# CarBee_v1_1.net
KiCad netlist of a schematic drawn in EAGLE
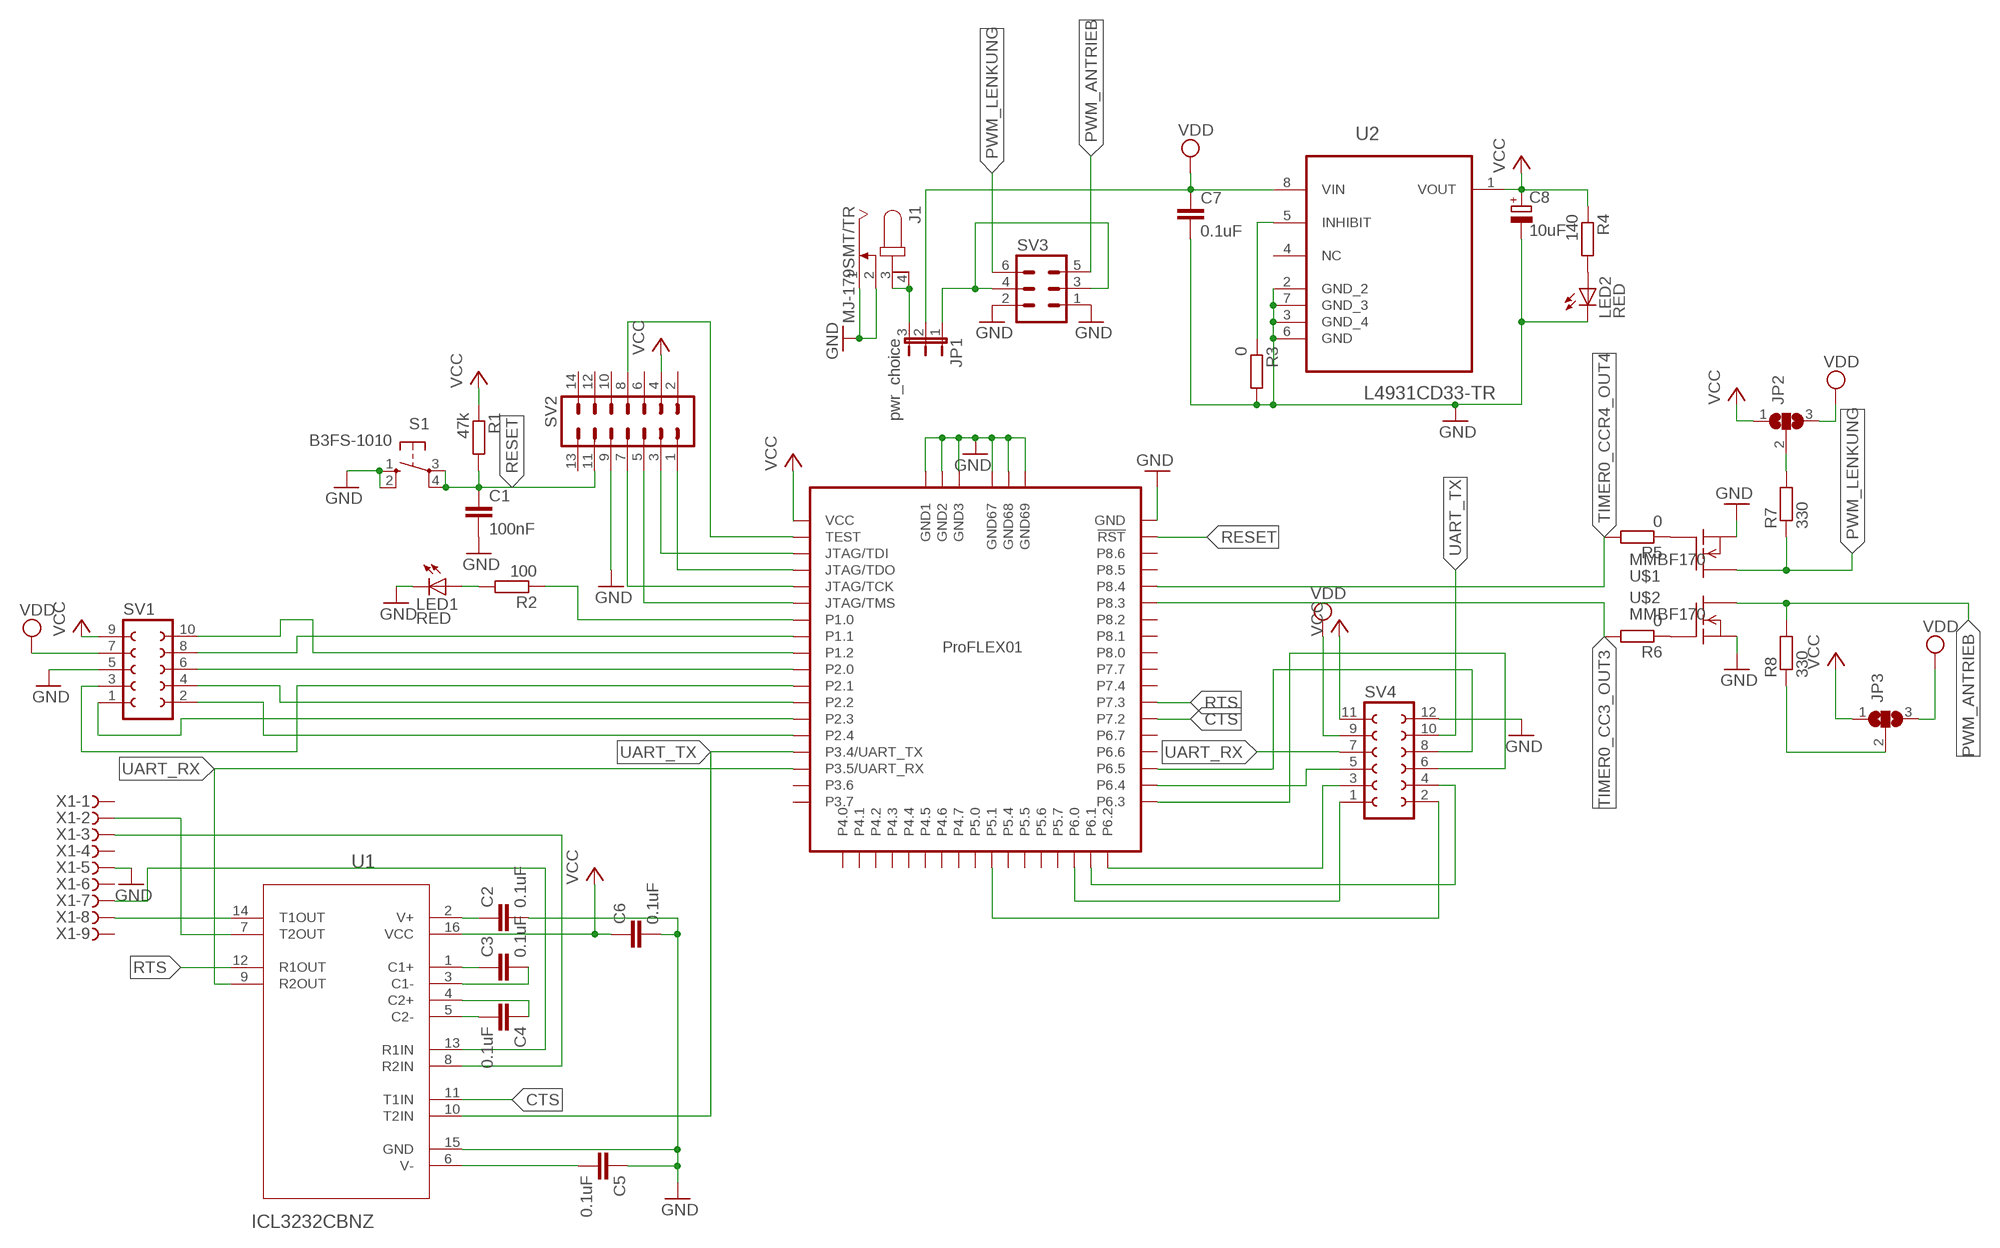
[diagram p0: schematic, sheet 1]

(export (version "E")
  (design (tool "Eeschema 10.0.6"))
  (components
    (comp (ref "C1")
      (value "100nF")
      (footprint "eagle-import:C0603")
      (fields (field (name "MPN") "0306ZC104KAT2A"))
      (libsource (lib "eagle-import") (part "C-EUC0603"))
    )
    (comp (ref "C2")
      (value "0.1uF")
      (footprint "eagle-import:C0603")
      (libsource (lib "eagle-import") (part "C-EUC0603"))
    )
    (comp (ref "C3")
      (value "0.1uF")
      (footprint "eagle-import:C0603")
      (fields (field (name "MPN") "0306ZC104KAT2A"))
      (libsource (lib "eagle-import") (part "C-EUC0603"))
    )
    (comp (ref "C4")
      (value "0.1uF")
      (footprint "eagle-import:C0603")
      (libsource (lib "eagle-import") (part "C-EUC0603"))
    )
    (comp (ref "C5")
      (value "0.1uF")
      (footprint "eagle-import:C0603")
      (libsource (lib "eagle-import") (part "C-EUC0603"))
    )
    (comp (ref "C6")
      (value "0.1uF")
      (footprint "eagle-import:C0603")
      (fields (field (name "MPN") "0306ZC104KAT2A"))
      (libsource (lib "eagle-import") (part "C-EUC0603"))
    )
    (comp (ref "C7")
      (value "0.1uF")
      (footprint "eagle-import:C0603")
      (libsource (lib "eagle-import") (part "C-EUC0603"))
    )
    (comp (ref "C8")
      (value "10uF")
      (footprint "eagle-import:PANASONIC_B")
      (libsource (lib "eagle-import") (part "CPOL-EU"))
    )
    (comp (ref "J1")
      (value "MJ-179SMT/TR")
      (footprint "eagle-import:MJ-179SMT")
      (libsource (lib "eagle-import") (part "MJ-179SMT/TR"))
    )
    (comp (ref "JP1")
      (value "pwr_choice")
      (footprint "eagle-import:JP2")
      (libsource (lib "eagle-import") (part "JP2E"))
    )
    (comp (ref "JP2")
      (value "SJ2W")
      (footprint "eagle-import:SJ_2")
      (libsource (lib "eagle-import") (part "SJ2W"))
    )
    (comp (ref "JP3")
      (value "SJ2W")
      (footprint "eagle-import:SJ_2")
      (libsource (lib "eagle-import") (part "SJ2W"))
    )
    (comp (ref "LED1")
      (value "RED")
      (footprint "eagle-import:CHIP-LED0603")
      (libsource (lib "eagle-import") (part "LEDCHIP-LED0603"))
    )
    (comp (ref "LED2")
      (value "RED")
      (footprint "eagle-import:CHIP-LED0603")
      (libsource (lib "eagle-import") (part "LEDCHIP-LED0603"))
    )
    (comp (ref "MOD1")
      (value "PROFLEX01")
      (footprint "eagle-import:MODFLEX01")
      (libsource (lib "eagle-import") (part "PROFLEX01"))
    )
    (comp (ref "R1")
      (value "47k")
      (footprint "eagle-import:R0603")
      (libsource (lib "eagle-import") (part "R-EU_R0603"))
    )
    (comp (ref "R2")
      (value "100")
      (footprint "eagle-import:R0603")
      (libsource (lib "eagle-import") (part "R-EU_R0603"))
    )
    (comp (ref "R3")
      (value "0")
      (footprint "eagle-import:R0603")
      (libsource (lib "eagle-import") (part "R-EU_R0603"))
    )
    (comp (ref "R4")
      (value "140")
      (footprint "eagle-import:R0603")
      (libsource (lib "eagle-import") (part "R-EU_R0603"))
    )
    (comp (ref "R5")
      (value "0")
      (footprint "eagle-import:R0603")
      (libsource (lib "eagle-import") (part "R-EU_R0603"))
    )
    (comp (ref "R6")
      (value "0")
      (footprint "eagle-import:R0603")
      (libsource (lib "eagle-import") (part "R-EU_R0603"))
    )
    (comp (ref "R7")
      (value "330")
      (footprint "eagle-import:R0603")
      (libsource (lib "eagle-import") (part "R-EU_R0603"))
    )
    (comp (ref "R8")
      (value "330")
      (footprint "eagle-import:R0603")
      (libsource (lib "eagle-import") (part "R-EU_R0603"))
    )
    (comp (ref "S1")
      (value "B3FS-1010")
      (footprint "eagle-import:B3FS-1010")
      (libsource (lib "eagle-import") (part "B3FS-1010"))
    )
    (comp (ref "SV1")
      (value "FE05-2")
      (footprint "eagle-import:FE05-2")
      (libsource (lib "eagle-import") (part "FE05-2"))
    )
    (comp (ref "SV2")
      (value "ML14")
      (footprint "eagle-import:ML14")
      (libsource (lib "eagle-import") (part "ML14"))
    )
    (comp (ref "SV3")
      (value "MA03-2")
      (footprint "eagle-import:MA03-2")
      (libsource (lib "eagle-import") (part "MA03-2"))
    )
    (comp (ref "SV4")
      (value "FE06-2")
      (footprint "eagle-import:FE06-2")
      (libsource (lib "eagle-import") (part "FE06-2"))
    )
    (comp (ref "U$1")
      (value "MMBF170")
      (footprint "eagle-import:SOT23")
      (libsource (lib "eagle-import") (part "MMBF170"))
    )
    (comp (ref "U$2")
      (value "MMBF170")
      (footprint "eagle-import:SOT23")
      (libsource (lib "eagle-import") (part "MMBF170"))
    )
    (comp (ref "U1")
      (value "ICL3232CBNZ")
      (footprint "eagle-import:SOIC127P600X175-16N")
      (libsource (lib "eagle-import") (part "ICL3232CBNZ"))
    )
    (comp (ref "U2")
      (value "L4931CD33-TR")
      (footprint "eagle-import:SOIC127P600X175-8N")
      (libsource (lib "eagle-import") (part "L4931CD33-TR"))
    )
    (comp (ref "X1")
      (value "F09HPS")
      (footprint "eagle-import:F09HP")
      (libsource (lib "eagle-import") (part "F09?SHP"))
    )
  )
  (nets
    (net (code "1") (name "CTS") (class "Default")
      (node (ref "MOD1") (pin "P$37") (pinfunction "P7.2_P$37") (pintype "bidirectional"))
      (node (ref "U1") (pin "11") (pinfunction "T1IN_11") (pintype "input"))
    )
    (net (code "2") (name "GND") (class "Default")
      (node (ref "C1") (pin "2") (pinfunction "2_2") (pintype "passive"))
      (node (ref "C2") (pin "2") (pinfunction "2_2") (pintype "passive"))
      (node (ref "C5") (pin "1") (pinfunction "1_1") (pintype "passive"))
      (node (ref "C6") (pin "2") (pinfunction "2_2") (pintype "passive"))
      (node (ref "C7") (pin "2") (pinfunction "2_2") (pintype "passive"))
      (node (ref "C8") (pin "-") (pinfunction "-_-") (pintype "passive"))
      (node (ref "J1") (pin "1") (pinfunction "1_1") (pintype "passive"))
      (node (ref "J1") (pin "2") (pinfunction "2_2") (pintype "passive"))
      (node (ref "LED1") (pin "C") (pinfunction "C_C") (pintype "passive"))
      (node (ref "LED2") (pin "C") (pinfunction "C_C") (pintype "passive"))
      (node (ref "MOD1") (pin "P$1") (pinfunction "GND1_P$1") (pintype "bidirectional"))
      (node (ref "MOD1") (pin "P$2") (pinfunction "GND2_P$2") (pintype "bidirectional"))
      (node (ref "MOD1") (pin "P$3") (pinfunction "GND3_P$3") (pintype "bidirectional"))
      (node (ref "MOD1") (pin "P$44") (pinfunction "GND_P$44") (pintype "bidirectional"))
      (node (ref "MOD1") (pin "P$67") (pinfunction "GND67_P$67") (pintype "bidirectional"))
      (node (ref "MOD1") (pin "P$68") (pinfunction "GND68_P$68") (pintype "bidirectional"))
      (node (ref "MOD1") (pin "P$69") (pinfunction "GND69_P$69") (pintype "bidirectional"))
      (node (ref "R3") (pin "2") (pinfunction "2_2") (pintype "passive"))
      (node (ref "S1") (pin "1") (pinfunction "S_1") (pintype "passive"))
      (node (ref "S1") (pin "2") (pinfunction "S1_2") (pintype "passive"))
      (node (ref "SV1") (pin "5") (pinfunction "5_5") (pintype "passive"))
      (node (ref "SV2") (pin "9") (pinfunction "9_9") (pintype "passive"))
      (node (ref "SV3") (pin "1") (pinfunction "1_1") (pintype "passive"))
      (node (ref "SV3") (pin "2") (pinfunction "2_2") (pintype "passive"))
      (node (ref "SV4") (pin "12") (pinfunction "12_12") (pintype "passive"))
      (node (ref "U$1") (pin "2") (pinfunction "S_2") (pintype "passive"))
      (node (ref "U$2") (pin "2") (pinfunction "S_2") (pintype "passive"))
      (node (ref "U1") (pin "15") (pinfunction "GND_15") (pintype "passive"))
      (node (ref "U2") (pin "2") (pinfunction "GND_2_2") (pintype "passive"))
      (node (ref "U2") (pin "3") (pinfunction "GND_4_3") (pintype "passive"))
      (node (ref "U2") (pin "6") (pinfunction "GND_6") (pintype "passive"))
      (node (ref "U2") (pin "7") (pinfunction "GND_3_7") (pintype "passive"))
      (node (ref "X1") (pin "5") (pinfunction "F_5") (pintype "passive"))
    )
    (net (code "3") (name "Net-(J1-Pad3)") (class "Default")
      (node (ref "J1") (pin "3") (pinfunction "3_3") (pintype "passive"))
      (node (ref "J1") (pin "4") (pinfunction "4_4") (pintype "passive"))
      (node (ref "JP1") (pin "3") (pinfunction "3_3") (pintype "passive"))
    )
    (net (code "4") (name "Net-(JP1-Pad1)") (class "Default")
      (node (ref "JP1") (pin "1") (pinfunction "1_1") (pintype "passive"))
      (node (ref "SV3") (pin "3") (pinfunction "3_3") (pintype "passive"))
      (node (ref "SV3") (pin "4") (pinfunction "4_4") (pintype "passive"))
    )
    (net (code "5") (name "Net-(JP2-Pad2)") (class "Default")
      (node (ref "JP2") (pin "2") (pinfunction "2_2") (pintype "passive"))
      (node (ref "R7") (pin "2") (pinfunction "2_2") (pintype "passive"))
    )
    (net (code "6") (name "Net-(JP3-Pad2)") (class "Default")
      (node (ref "JP3") (pin "2") (pinfunction "2_2") (pintype "passive"))
      (node (ref "R8") (pin "1") (pinfunction "1_1") (pintype "passive"))
    )
    (net (code "7") (name "Net-(LED1-PadA)") (class "Default")
      (node (ref "LED1") (pin "A") (pinfunction "A_A") (pintype "passive"))
      (node (ref "R2") (pin "2") (pinfunction "2_2") (pintype "passive"))
    )
    (net (code "8") (name "Net-(LED2-PadA)") (class "Default")
      (node (ref "LED2") (pin "A") (pinfunction "A_A") (pintype "passive"))
      (node (ref "R4") (pin "2") (pinfunction "2_2") (pintype "passive"))
    )
    (net (code "9") (name "Net-(MOD1-JTAG{slash}TCK)") (class "Default")
      (node (ref "MOD1") (pin "P$11") (pinfunction "JTAG/TCK_P$11") (pintype "bidirectional"))
      (node (ref "SV2") (pin "7") (pinfunction "7_7") (pintype "passive"))
    )
    (net (code "10") (name "Net-(MOD1-JTAG{slash}TDI)") (class "Default")
      (node (ref "MOD1") (pin "P$10") (pinfunction "JTAG/TDI_P$10") (pintype "bidirectional"))
      (node (ref "SV2") (pin "3") (pinfunction "3_3") (pintype "passive"))
    )
    (net (code "11") (name "Net-(MOD1-JTAG{slash}TDO)") (class "Default")
      (node (ref "MOD1") (pin "P$12") (pinfunction "JTAG/TDO_P$12") (pintype "bidirectional"))
      (node (ref "SV2") (pin "1") (pinfunction "1_1") (pintype "passive"))
    )
    (net (code "12") (name "Net-(MOD1-JTAG{slash}TMS)") (class "Default")
      (node (ref "MOD1") (pin "P$9") (pinfunction "JTAG/TMS_P$9") (pintype "bidirectional"))
      (node (ref "SV2") (pin "5") (pinfunction "5_5") (pintype "passive"))
    )
    (net (code "13") (name "Net-(MOD1-P1.0)") (class "Default")
      (node (ref "MOD1") (pin "P$49") (pinfunction "P1.0_P$49") (pintype "bidirectional"))
      (node (ref "R2") (pin "1") (pinfunction "1_1") (pintype "passive"))
    )
    (net (code "14") (name "Net-(MOD1-P1.1)") (class "Default")
      (node (ref "MOD1") (pin "P$50") (pinfunction "P1.1_P$50") (pintype "bidirectional"))
      (node (ref "SV1") (pin "8") (pinfunction "8_8") (pintype "passive"))
    )
    (net (code "15") (name "Net-(MOD1-P1.2)") (class "Default")
      (node (ref "MOD1") (pin "P$47") (pinfunction "P1.2_P$47") (pintype "bidirectional"))
      (node (ref "SV1") (pin "10") (pinfunction "10_10") (pintype "passive"))
    )
    (net (code "16") (name "Net-(MOD1-P2.0)") (class "Default")
      (node (ref "MOD1") (pin "P$51") (pinfunction "P2.0_P$51") (pintype "bidirectional"))
      (node (ref "SV1") (pin "6") (pinfunction "6_6") (pintype "passive"))
    )
    (net (code "17") (name "Net-(MOD1-P2.1)") (class "Default")
      (node (ref "MOD1") (pin "P$52") (pinfunction "P2.1_P$52") (pintype "bidirectional"))
      (node (ref "SV1") (pin "3") (pinfunction "3_3") (pintype "passive"))
    )
    (net (code "18") (name "Net-(MOD1-P2.2)") (class "Default")
      (node (ref "MOD1") (pin "P$53") (pinfunction "P2.2_P$53") (pintype "bidirectional"))
      (node (ref "SV1") (pin "4") (pinfunction "4_4") (pintype "passive"))
    )
    (net (code "19") (name "Net-(MOD1-P2.3)") (class "Default")
      (node (ref "MOD1") (pin "P$54") (pinfunction "P2.3_P$54") (pintype "bidirectional"))
      (node (ref "SV1") (pin "1") (pinfunction "1_1") (pintype "passive"))
    )
    (net (code "20") (name "Net-(MOD1-P2.4)") (class "Default")
      (node (ref "MOD1") (pin "P$55") (pinfunction "P2.4_P$55") (pintype "bidirectional"))
      (node (ref "SV1") (pin "2") (pinfunction "2_2") (pintype "passive"))
    )
    (net (code "21") (name "Net-(MOD1-P5.1)") (class "Default")
      (node (ref "MOD1") (pin "P$16") (pinfunction "P5.1_P$16") (pintype "bidirectional"))
      (node (ref "SV4") (pin "2") (pinfunction "2_2") (pintype "passive"))
    )
    (net (code "22") (name "Net-(MOD1-P6.0)") (class "Default")
      (node (ref "MOD1") (pin "P$17") (pinfunction "P6.0_P$17") (pintype "bidirectional"))
      (node (ref "SV4") (pin "1") (pinfunction "1_1") (pintype "passive"))
    )
    (net (code "23") (name "Net-(MOD1-P6.1)") (class "Default")
      (node (ref "MOD1") (pin "P$18") (pinfunction "P6.1_P$18") (pintype "bidirectional"))
      (node (ref "SV4") (pin "4") (pinfunction "4_4") (pintype "passive"))
    )
    (net (code "24") (name "Net-(MOD1-P6.2)") (class "Default")
      (node (ref "MOD1") (pin "P$19") (pinfunction "P6.2_P$19") (pintype "bidirectional"))
      (node (ref "SV4") (pin "3") (pinfunction "3_3") (pintype "passive"))
    )
    (net (code "25") (name "Net-(MOD1-P6.3)") (class "Default")
      (node (ref "MOD1") (pin "P$20") (pinfunction "P6.3_P$20") (pintype "bidirectional"))
      (node (ref "SV4") (pin "6") (pinfunction "6_6") (pintype "passive"))
    )
    (net (code "26") (name "Net-(MOD1-P6.4)") (class "Default")
      (node (ref "MOD1") (pin "P$21") (pinfunction "P6.4_P$21") (pintype "bidirectional"))
      (node (ref "SV4") (pin "5") (pinfunction "5_5") (pintype "passive"))
    )
    (net (code "27") (name "Net-(MOD1-P6.5)") (class "Default")
      (node (ref "MOD1") (pin "P$22") (pinfunction "P6.5_P$22") (pintype "bidirectional"))
      (node (ref "SV4") (pin "8") (pinfunction "8_8") (pintype "passive"))
    )
    (net (code "28") (name "Net-(MOD1-TEST)") (class "Default")
      (node (ref "MOD1") (pin "P$13") (pinfunction "TEST_P$13") (pintype "bidirectional"))
      (node (ref "SV2") (pin "8") (pinfunction "8_8") (pintype "passive"))
    )
    (net (code "29") (name "Net-(U$1-G)") (class "Default")
      (node (ref "R5") (pin "1") (pinfunction "1_1") (pintype "passive"))
      (node (ref "U$1") (pin "1") (pinfunction "G_1") (pintype "passive"))
    )
    (net (code "30") (name "Net-(U$2-G)") (class "Default")
      (node (ref "R6") (pin "1") (pinfunction "1_1") (pintype "passive"))
      (node (ref "U$2") (pin "1") (pinfunction "G_1") (pintype "passive"))
    )
    (net (code "31") (name "Net-(U1-C1+)") (class "Default")
      (node (ref "C3") (pin "1") (pinfunction "1_1") (pintype "passive"))
      (node (ref "U1") (pin "1") (pinfunction "C1+_1") (pintype "passive"))
    )
    (net (code "32") (name "Net-(U1-C1-)") (class "Default")
      (node (ref "C3") (pin "2") (pinfunction "2_2") (pintype "passive"))
      (node (ref "U1") (pin "3") (pinfunction "C1-_3") (pintype "passive"))
    )
    (net (code "33") (name "Net-(U1-C2+)") (class "Default")
      (node (ref "C4") (pin "1") (pinfunction "1_1") (pintype "passive"))
      (node (ref "U1") (pin "4") (pinfunction "C2+_4") (pintype "passive"))
    )
    (net (code "34") (name "Net-(U1-C2-)") (class "Default")
      (node (ref "C4") (pin "2") (pinfunction "2_2") (pintype "passive"))
      (node (ref "U1") (pin "5") (pinfunction "C2-_5") (pintype "passive"))
    )
    (net (code "35") (name "Net-(U1-R1IN)") (class "Default")
      (node (ref "U1") (pin "13") (pinfunction "R1IN_13") (pintype "input"))
      (node (ref "X1") (pin "7") (pinfunction "F_7") (pintype "passive"))
    )
    (net (code "36") (name "Net-(U1-R2IN)") (class "Default")
      (node (ref "U1") (pin "8") (pinfunction "R2IN_8") (pintype "input"))
      (node (ref "X1") (pin "3") (pinfunction "F_3") (pintype "passive"))
    )
    (net (code "37") (name "Net-(U1-T1OUT)") (class "Default")
      (node (ref "U1") (pin "14") (pinfunction "T1OUT_14") (pintype "output"))
      (node (ref "X1") (pin "8") (pinfunction "F_8") (pintype "passive"))
    )
    (net (code "38") (name "Net-(U1-T2OUT)") (class "Default")
      (node (ref "U1") (pin "7") (pinfunction "T2OUT_7") (pintype "output"))
      (node (ref "X1") (pin "2") (pinfunction "F_2") (pintype "passive"))
    )
    (net (code "39") (name "Net-(U1-V+)") (class "Default")
      (node (ref "C2") (pin "1") (pinfunction "1_1") (pintype "passive"))
      (node (ref "U1") (pin "2") (pinfunction "V+_2") (pintype "input"))
    )
    (net (code "40") (name "Net-(U1-V-)") (class "Default")
      (node (ref "C5") (pin "2") (pinfunction "2_2") (pintype "passive"))
      (node (ref "U1") (pin "6") (pinfunction "V-_6") (pintype "input"))
    )
    (net (code "41") (name "Net-(U2-INHIBIT)") (class "Default")
      (node (ref "R3") (pin "1") (pinfunction "1_1") (pintype "passive"))
      (node (ref "U2") (pin "5") (pinfunction "INHIBIT_5") (pintype "passive"))
    )
    (net (code "42") (name "PWM_ANTRIEB") (class "Default")
      (node (ref "R8") (pin "2") (pinfunction "2_2") (pintype "passive"))
      (node (ref "SV3") (pin "5") (pinfunction "5_5") (pintype "passive"))
      (node (ref "U$2") (pin "3") (pinfunction "D_3") (pintype "passive"))
    )
    (net (code "43") (name "PWM_LENKUNG") (class "Default")
      (node (ref "R7") (pin "1") (pinfunction "1_1") (pintype "passive"))
      (node (ref "SV3") (pin "6") (pinfunction "6_6") (pintype "passive"))
      (node (ref "U$1") (pin "3") (pinfunction "D_3") (pintype "passive"))
    )
    (net (code "44") (name "RESET") (class "Default")
      (node (ref "C1") (pin "1") (pinfunction "1_1") (pintype "passive"))
      (node (ref "MOD1") (pin "P$14") (pinfunction "~{RST}_P$14") (pintype "bidirectional"))
      (node (ref "R1") (pin "2") (pinfunction "2_2") (pintype "passive"))
      (node (ref "S1") (pin "3") (pinfunction "P_3") (pintype "passive"))
      (node (ref "S1") (pin "4") (pinfunction "P1_4") (pintype "passive"))
      (node (ref "SV2") (pin "11") (pinfunction "11_11") (pintype "passive"))
    )
    (net (code "45") (name "RTS") (class "Default")
      (node (ref "MOD1") (pin "P$38") (pinfunction "P7.3_P$38") (pintype "bidirectional"))
      (node (ref "U1") (pin "12") (pinfunction "R1OUT_12") (pintype "output"))
    )
    (net (code "46") (name "TIMER0_CC3_OUT3") (class "Default")
      (node (ref "MOD1") (pin "P$42") (pinfunction "P8.3_P$42") (pintype "bidirectional"))
      (node (ref "R6") (pin "2") (pinfunction "2_2") (pintype "passive"))
    )
    (net (code "47") (name "TIMER0_CCR4_OUT4") (class "Default")
      (node (ref "MOD1") (pin "P$41") (pinfunction "P8.4_P$41") (pintype "bidirectional"))
      (node (ref "R5") (pin "2") (pinfunction "2_2") (pintype "passive"))
    )
    (net (code "48") (name "UART_RX") (class "Default")
      (node (ref "MOD1") (pin "P$36") (pinfunction "P3.5/UART_RX_P$36") (pintype "bidirectional"))
      (node (ref "SV4") (pin "7") (pinfunction "7_7") (pintype "passive"))
      (node (ref "U1") (pin "9") (pinfunction "R2OUT_9") (pintype "output"))
    )
    (net (code "49") (name "UART_TX") (class "Default")
      (node (ref "MOD1") (pin "P$35") (pinfunction "P3.4/UART_TX_P$35") (pintype "bidirectional"))
      (node (ref "SV4") (pin "10") (pinfunction "10_10") (pintype "passive"))
      (node (ref "U1") (pin "10") (pinfunction "T2IN_10") (pintype "input"))
    )
    (net (code "50") (name "VCC") (class "Default")
      (node (ref "C6") (pin "1") (pinfunction "1_1") (pintype "passive"))
      (node (ref "C8") (pin "+") (pinfunction "+_+") (pintype "passive"))
      (node (ref "JP2") (pin "1") (pinfunction "1_1") (pintype "passive"))
      (node (ref "JP3") (pin "1") (pinfunction "1_1") (pintype "passive"))
      (node (ref "MOD1") (pin "P$26") (pinfunction "VCC_P$26") (pintype "bidirectional"))
      (node (ref "R1") (pin "1") (pinfunction "1_1") (pintype "passive"))
      (node (ref "R4") (pin "1") (pinfunction "1_1") (pintype "passive"))
      (node (ref "SV1") (pin "9") (pinfunction "9_9") (pintype "passive"))
      (node (ref "SV2") (pin "4") (pinfunction "4_4") (pintype "passive"))
      (node (ref "SV4") (pin "11") (pinfunction "11_11") (pintype "passive"))
      (node (ref "U1") (pin "16") (pinfunction "VCC_16") (pintype "power_in"))
      (node (ref "U2") (pin "1") (pinfunction "VOUT_1") (pintype "power_in"))
    )
    (net (code "51") (name "VDD") (class "Default")
      (node (ref "C7") (pin "1") (pinfunction "1_1") (pintype "passive"))
      (node (ref "JP1") (pin "2") (pinfunction "2_2") (pintype "passive"))
      (node (ref "JP2") (pin "3") (pinfunction "3_3") (pintype "passive"))
      (node (ref "JP3") (pin "3") (pinfunction "3_3") (pintype "passive"))
      (node (ref "SV1") (pin "7") (pinfunction "7_7") (pintype "passive"))
      (node (ref "SV4") (pin "9") (pinfunction "9_9") (pintype "passive"))
      (node (ref "U2") (pin "8") (pinfunction "VIN_8") (pintype "power_in"))
    )
    (net (code "52") (name "unconnected-(MOD1-P3.6-PadP$59)") (class "Default")
      (node (ref "MOD1") (pin "P$59") (pinfunction "P3.6_P$59") (pintype "bidirectional"))
    )
    (net (code "53") (name "unconnected-(MOD1-P3.7-PadP$57)") (class "Default")
      (node (ref "MOD1") (pin "P$57") (pinfunction "P3.7_P$57") (pintype "bidirectional"))
    )
    (net (code "54") (name "unconnected-(MOD1-P4.0-PadP$34)") (class "Default")
      (node (ref "MOD1") (pin "P$34") (pinfunction "P4.0_P$34") (pintype "bidirectional"))
    )
    (net (code "55") (name "unconnected-(MOD1-P4.1-PadP$33)") (class "Default")
      (node (ref "MOD1") (pin "P$33") (pinfunction "P4.1_P$33") (pintype "bidirectional"))
    )
    (net (code "56") (name "unconnected-(MOD1-P4.2-PadP$32)") (class "Default")
      (node (ref "MOD1") (pin "P$32") (pinfunction "P4.2_P$32") (pintype "bidirectional"))
    )
    (net (code "57") (name "unconnected-(MOD1-P4.3-PadP$31)") (class "Default")
      (node (ref "MOD1") (pin "P$31") (pinfunction "P4.3_P$31") (pintype "bidirectional"))
    )
    (net (code "58") (name "unconnected-(MOD1-P4.4-PadP$30)") (class "Default")
      (node (ref "MOD1") (pin "P$30") (pinfunction "P4.4_P$30") (pintype "bidirectional"))
    )
    (net (code "59") (name "unconnected-(MOD1-P4.5-PadP$29)") (class "Default")
      (node (ref "MOD1") (pin "P$29") (pinfunction "P4.5_P$29") (pintype "bidirectional"))
    )
    (net (code "60") (name "unconnected-(MOD1-P4.6-PadP$28)") (class "Default")
      (node (ref "MOD1") (pin "P$28") (pinfunction "P4.6_P$28") (pintype "bidirectional"))
    )
    (net (code "61") (name "unconnected-(MOD1-P4.7-PadP$27)") (class "Default")
      (node (ref "MOD1") (pin "P$27") (pinfunction "P4.7_P$27") (pintype "bidirectional"))
    )
    (net (code "62") (name "unconnected-(MOD1-P5.0-PadP$15)") (class "Default")
      (node (ref "MOD1") (pin "P$15") (pinfunction "P5.0_P$15") (pintype "bidirectional"))
    )
    (net (code "63") (name "unconnected-(MOD1-P5.4-PadP$56)") (class "Default")
      (node (ref "MOD1") (pin "P$56") (pinfunction "P5.4_P$56") (pintype "bidirectional"))
    )
    (net (code "64") (name "unconnected-(MOD1-P5.5-PadP$58)") (class "Default")
      (node (ref "MOD1") (pin "P$58") (pinfunction "P5.5_P$58") (pintype "bidirectional"))
    )
    (net (code "65") (name "unconnected-(MOD1-P5.6-PadP$61)") (class "Default")
      (node (ref "MOD1") (pin "P$61") (pinfunction "P5.6_P$61") (pintype "bidirectional"))
    )
    (net (code "66") (name "unconnected-(MOD1-P5.7-PadP$60)") (class "Default")
      (node (ref "MOD1") (pin "P$60") (pinfunction "P5.7_P$60") (pintype "bidirectional"))
    )
    (net (code "67") (name "unconnected-(MOD1-P6.6-PadP$23)") (class "Default")
      (node (ref "MOD1") (pin "P$23") (pinfunction "P6.6_P$23") (pintype "bidirectional"))
    )
    (net (code "68") (name "unconnected-(MOD1-P6.7-PadP$24)") (class "Default")
      (node (ref "MOD1") (pin "P$24") (pinfunction "P6.7_P$24") (pintype "bidirectional"))
    )
    (net (code "69") (name "unconnected-(MOD1-P7.4-PadP$25)") (class "Default")
      (node (ref "MOD1") (pin "P$25") (pinfunction "P7.4_P$25") (pintype "bidirectional"))
    )
    (net (code "70") (name "unconnected-(MOD1-P7.7-PadP$48)") (class "Default")
      (node (ref "MOD1") (pin "P$48") (pinfunction "P7.7_P$48") (pintype "bidirectional"))
    )
    (net (code "71") (name "unconnected-(MOD1-P8.0-PadP$46)") (class "Default")
      (node (ref "MOD1") (pin "P$46") (pinfunction "P8.0_P$46") (pintype "bidirectional"))
    )
    (net (code "72") (name "unconnected-(MOD1-P8.1-PadP$45)") (class "Default")
      (node (ref "MOD1") (pin "P$45") (pinfunction "P8.1_P$45") (pintype "bidirectional"))
    )
    (net (code "73") (name "unconnected-(MOD1-P8.2-PadP$43)") (class "Default")
      (node (ref "MOD1") (pin "P$43") (pinfunction "P8.2_P$43") (pintype "bidirectional"))
    )
    (net (code "74") (name "unconnected-(MOD1-P8.5-PadP$40)") (class "Default")
      (node (ref "MOD1") (pin "P$40") (pinfunction "P8.5_P$40") (pintype "bidirectional"))
    )
    (net (code "75") (name "unconnected-(MOD1-P8.6-PadP$39)") (class "Default")
      (node (ref "MOD1") (pin "P$39") (pinfunction "P8.6_P$39") (pintype "bidirectional"))
    )
    (net (code "76") (name "unconnected-(SV2-Pad2)") (class "Default")
      (node (ref "SV2") (pin "2") (pinfunction "2_2") (pintype "passive"))
    )
    (net (code "77") (name "unconnected-(SV2-Pad6)") (class "Default")
      (node (ref "SV2") (pin "6") (pinfunction "6_6") (pintype "passive"))
    )
    (net (code "78") (name "unconnected-(SV2-Pad10)") (class "Default")
      (node (ref "SV2") (pin "10") (pinfunction "10_10") (pintype "passive"))
    )
    (net (code "79") (name "unconnected-(SV2-Pad12)") (class "Default")
      (node (ref "SV2") (pin "12") (pinfunction "12_12") (pintype "passive"))
    )
    (net (code "80") (name "unconnected-(SV2-Pad13)") (class "Default")
      (node (ref "SV2") (pin "13") (pinfunction "13_13") (pintype "passive"))
    )
    (net (code "81") (name "unconnected-(SV2-Pad14)") (class "Default")
      (node (ref "SV2") (pin "14") (pinfunction "14_14") (pintype "passive"))
    )
    (net (code "82") (name "unconnected-(U2-NC-Pad4)") (class "Default")
      (node (ref "U2") (pin "4") (pinfunction "NC_4") (pintype "no_connect"))
    )
    (net (code "83") (name "unconnected-(X1A-F-Pad1)") (class "Default")
      (node (ref "X1") (pin "1") (pinfunction "F_1") (pintype "passive"))
    )
    (net (code "84") (name "unconnected-(X1D-F-Pad4)") (class "Default")
      (node (ref "X1") (pin "4") (pinfunction "F_4") (pintype "passive"))
    )
    (net (code "85") (name "unconnected-(X1F-F-Pad6)") (class "Default")
      (node (ref "X1") (pin "6") (pinfunction "F_6") (pintype "passive"))
    )
    (net (code "86") (name "unconnected-(X1I-F-Pad9)") (class "Default")
      (node (ref "X1") (pin "9") (pinfunction "F_9") (pintype "passive"))
    )
  )
)
